# SCH_MR60FDA1_60GHz_Radar_to_FTDI_Adapter.net
KiCad netlist of a schematic drawn in Altium Designer
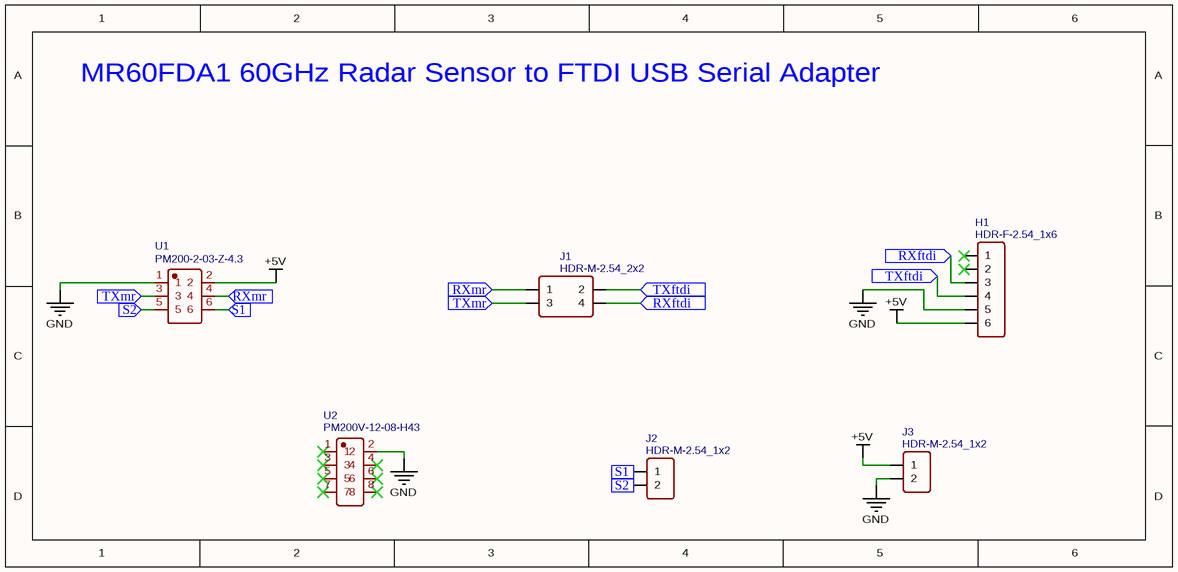
[diagram p0: SCH_MR60FDA1 60GHz Radar to FTDI Adapter_2023-03-13.schdoc]

(export (version "E")
  (design (tool "Eeschema 10.0.6"))
  (components
    (comp (ref "H1")
      (value "HDR-F-2.54_1x6")
      (fields (field (name "BOM_SUPPLIER PART") "C40877") (field (name "CONTRIBUTOR") "LCEDA_Lib"))
      (libsource (lib "altium-import") (part "root_0_HDR-F-2.54_1x6_"))
    )
    (comp (ref "J1")
      (value "HDR-M-2.54_2x2")
      (fields (field (name "BOM_SUPPLIER PART") "C66690") (field (name "CONTRIBUTOR") "LCEDA_Lib"))
      (libsource (lib "altium-import") (part "root_0_HDR-M-2.54_2x2_"))
    )
    (comp (ref "J2")
      (value "HDR-M-2.54_1x2")
      (fields (field (name "BOM_SUPPLIER PART") "C124375") (field (name "CONTRIBUTOR") "LCEDA_Lib"))
      (libsource (lib "altium-import") (part "root_0_HDR-M-2.54_1x2_"))
    )
    (comp (ref "J3")
      (value "HDR-M-2.54_1x2")
      (fields (field (name "BOM_SUPPLIER PART") "C124375") (field (name "CONTRIBUTOR") "LCEDA_Lib"))
      (libsource (lib "altium-import") (part "root_0_HDR-M-2.54_1x2_"))
    )
    (comp (ref "U1")
      (value "PM200-2-03-Z-4.3")
      (fields (field (name "BOM_SUPPLIER PART") "C2906071") (field (name "CONTRIBUTOR") "LCSC"))
      (libsource (lib "altium-import") (part "root_0_PM200-2-03-Z-4.3_"))
    )
    (comp (ref "U2")
      (value "PM200V-12-08-H43")
      (fields (field (name "BOM_SUPPLIER PART") "C2925563") (field (name "CONTRIBUTOR") "LCSC"))
      (libsource (lib "altium-import") (part "root_0_PM200V-12-08-H43_"))
    )
  )
  (nets
    (net (code "1") (name "+5V") (class "Default")
      (node (ref "H1") (pin "6") (pinfunction "6_6") (pintype "passive"))
      (node (ref "J3") (pin "1") (pinfunction "1_1") (pintype "passive"))
      (node (ref "U1") (pin "2") (pinfunction "2_2") (pintype "passive"))
    )
    (net (code "2") (name "/RXftdi") (class "Default")
      (node (ref "H1") (pin "3") (pinfunction "3_3") (pintype "passive"))
      (node (ref "J1") (pin "4") (pinfunction "4_4") (pintype "passive"))
    )
    (net (code "3") (name "/RXmr") (class "Default")
      (node (ref "J1") (pin "1") (pinfunction "1_1") (pintype "passive"))
      (node (ref "U1") (pin "4") (pinfunction "4_4") (pintype "passive"))
    )
    (net (code "4") (name "/S1") (class "Default")
      (node (ref "J2") (pin "1") (pinfunction "1_1") (pintype "passive"))
      (node (ref "U1") (pin "6") (pinfunction "6_6") (pintype "passive"))
    )
    (net (code "5") (name "/S2") (class "Default")
      (node (ref "J2") (pin "2") (pinfunction "2_2") (pintype "passive"))
      (node (ref "U1") (pin "5") (pinfunction "5_5") (pintype "passive"))
    )
    (net (code "6") (name "/TXftdi") (class "Default")
      (node (ref "H1") (pin "4") (pinfunction "4_4") (pintype "passive"))
      (node (ref "J1") (pin "2") (pinfunction "2_2") (pintype "passive"))
    )
    (net (code "7") (name "/TXmr") (class "Default")
      (node (ref "J1") (pin "3") (pinfunction "3_3") (pintype "passive"))
      (node (ref "U1") (pin "3") (pinfunction "3_3") (pintype "passive"))
    )
    (net (code "8") (name "GND") (class "Default")
      (node (ref "H1") (pin "5") (pinfunction "5_5") (pintype "passive"))
      (node (ref "J3") (pin "2") (pinfunction "2_2") (pintype "passive"))
      (node (ref "U1") (pin "1") (pinfunction "1_1") (pintype "passive"))
      (node (ref "U2") (pin "2") (pinfunction "2_2") (pintype "passive"))
    )
    (net (code "9") (name "unconnected-(H1-Pad1)") (class "Default")
      (node (ref "H1") (pin "1") (pinfunction "1_1") (pintype "passive+no_connect"))
    )
    (net (code "10") (name "unconnected-(H1-Pad2)") (class "Default")
      (node (ref "H1") (pin "2") (pinfunction "2_2") (pintype "passive+no_connect"))
    )
    (net (code "11") (name "unconnected-(U2-Pad1)") (class "Default")
      (node (ref "U2") (pin "1") (pinfunction "1_1") (pintype "passive+no_connect"))
    )
    (net (code "12") (name "unconnected-(U2-Pad3)") (class "Default")
      (node (ref "U2") (pin "3") (pinfunction "3_3") (pintype "passive+no_connect"))
    )
    (net (code "13") (name "unconnected-(U2-Pad4)") (class "Default")
      (node (ref "U2") (pin "4") (pinfunction "4_4") (pintype "passive+no_connect"))
    )
    (net (code "14") (name "unconnected-(U2-Pad5)") (class "Default")
      (node (ref "U2") (pin "5") (pinfunction "5_5") (pintype "passive+no_connect"))
    )
    (net (code "15") (name "unconnected-(U2-Pad6)") (class "Default")
      (node (ref "U2") (pin "6") (pinfunction "6_6") (pintype "passive+no_connect"))
    )
    (net (code "16") (name "unconnected-(U2-Pad7)") (class "Default")
      (node (ref "U2") (pin "7") (pinfunction "7_7") (pintype "passive+no_connect"))
    )
    (net (code "17") (name "unconnected-(U2-Pad8)") (class "Default")
      (node (ref "U2") (pin "8") (pinfunction "8_8") (pintype "passive+no_connect"))
    )
  )
)
